# Power-Monitor-Module.net
KiCad netlist of a schematic drawn in EAGLE
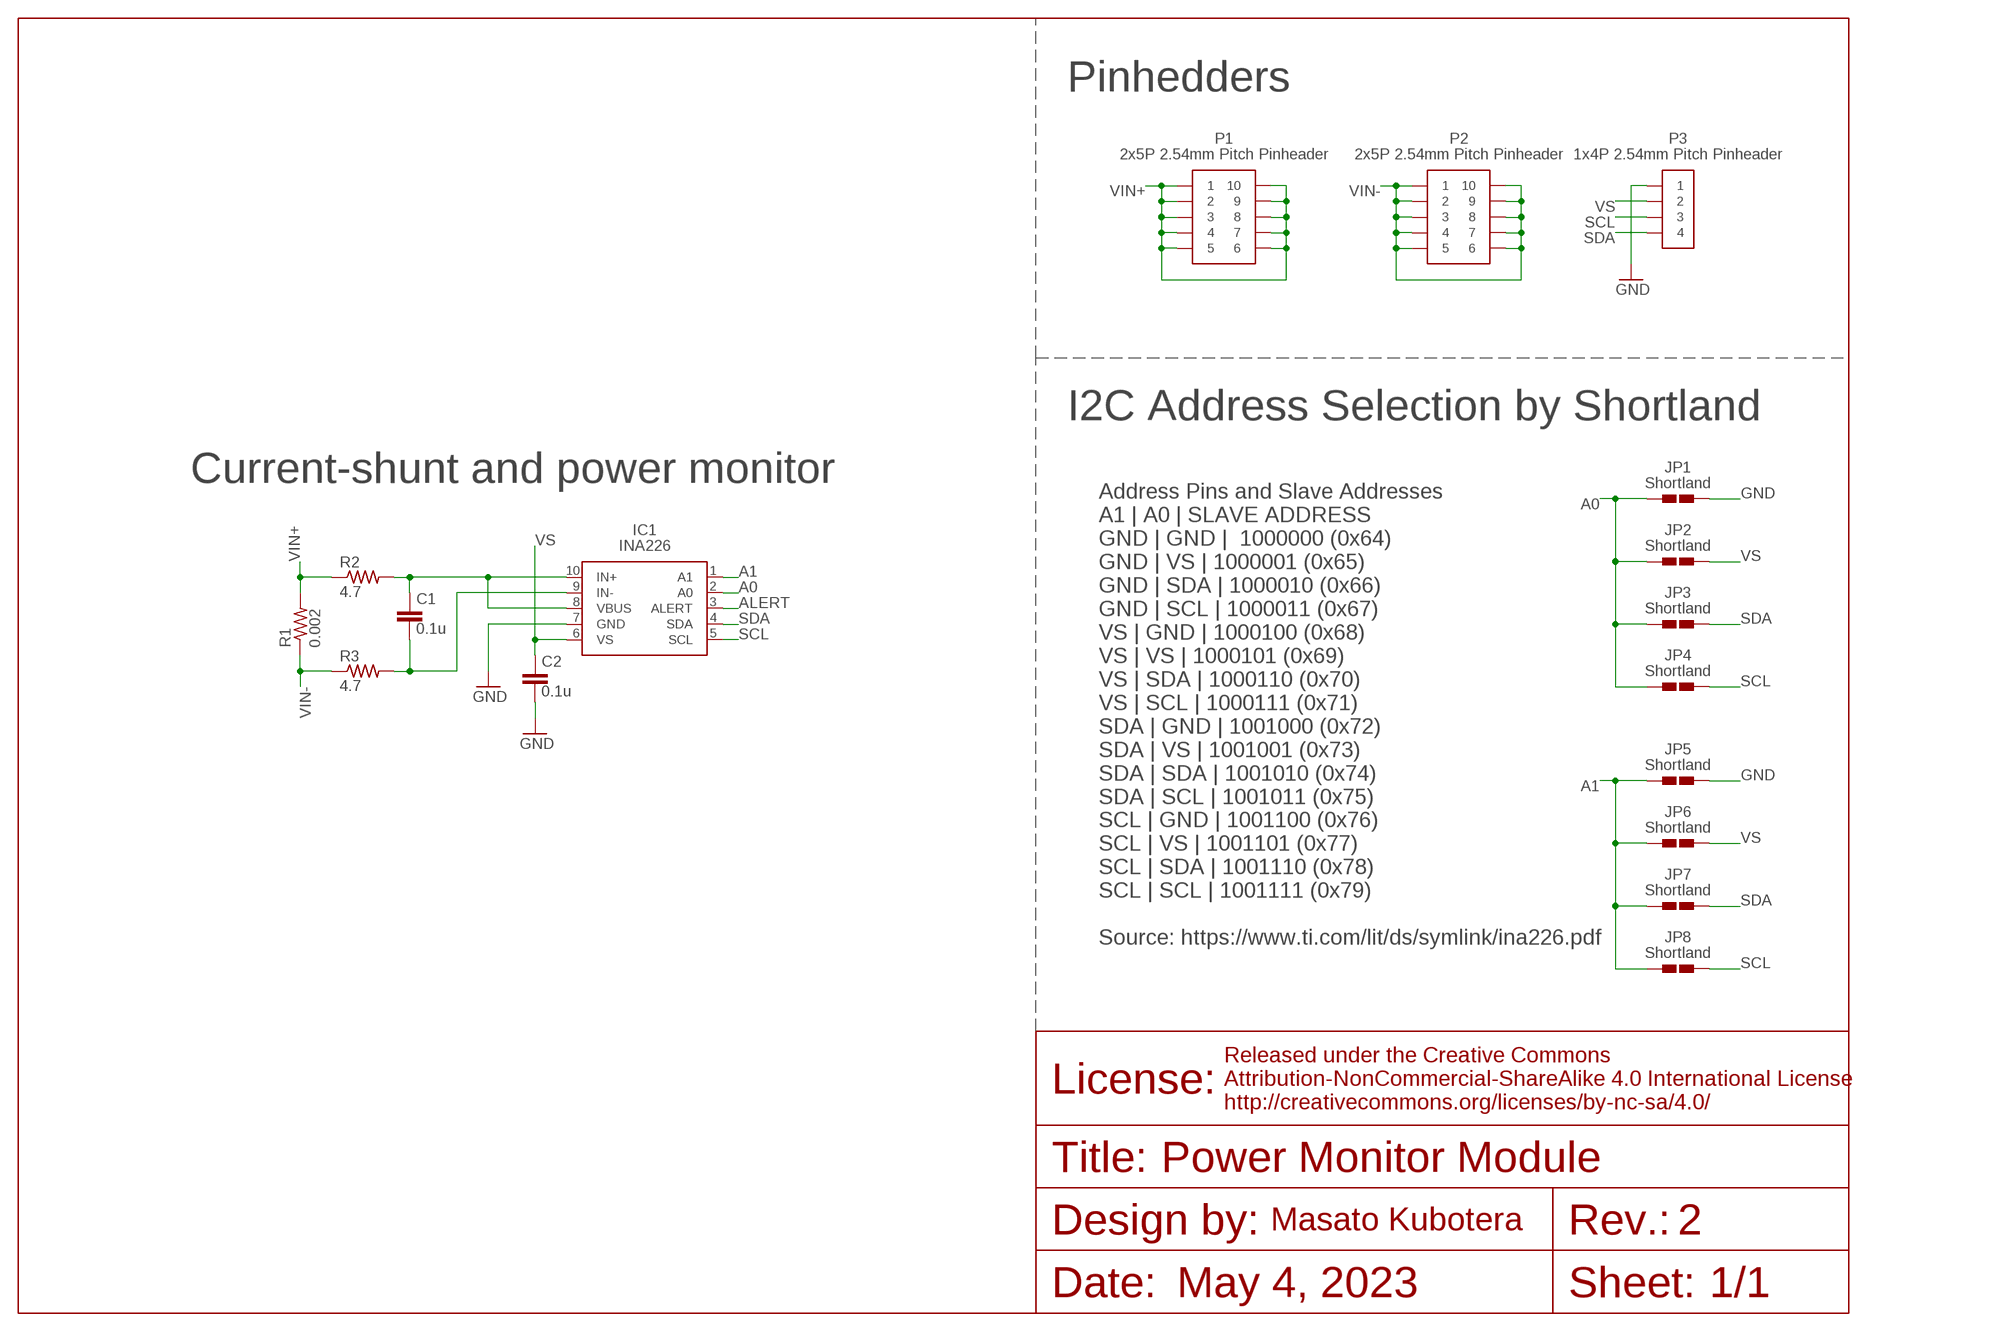
[diagram p0: schematic, sheet 1]

(export (version "E")
  (design (tool "Eeschema 10.0.6"))
  (components
    (comp (ref "C1")
      (value "0.1u")
      (footprint "eagle-import:C0402")
      (libsource (lib "eagle-import") (part "C-EUC0402"))
    )
    (comp (ref "C2")
      (value "0.1u")
      (footprint "eagle-import:C0402")
      (libsource (lib "eagle-import") (part "C-EUC0402"))
    )
    (comp (ref "IC1")
      (value "INA226")
      (footprint "eagle-import:MSOP-10")
      (libsource (lib "eagle-import") (part "INA226"))
    )
    (comp (ref "JP1")
      (value "SHORTLAND")
      (footprint "eagle-import:SHORTLAND")
      (libsource (lib "eagle-import") (part "SHORTLAND"))
    )
    (comp (ref "JP2")
      (value "SHORTLAND")
      (footprint "eagle-import:SHORTLAND")
      (libsource (lib "eagle-import") (part "SHORTLAND"))
    )
    (comp (ref "JP3")
      (value "SHORTLAND")
      (footprint "eagle-import:SHORTLAND")
      (libsource (lib "eagle-import") (part "SHORTLAND"))
    )
    (comp (ref "JP4")
      (value "SHORTLAND")
      (footprint "eagle-import:SHORTLAND")
      (libsource (lib "eagle-import") (part "SHORTLAND"))
    )
    (comp (ref "JP5")
      (value "SHORTLAND")
      (footprint "eagle-import:SHORTLAND")
      (libsource (lib "eagle-import") (part "SHORTLAND"))
    )
    (comp (ref "JP6")
      (value "SHORTLAND")
      (footprint "eagle-import:SHORTLAND")
      (libsource (lib "eagle-import") (part "SHORTLAND"))
    )
    (comp (ref "JP7")
      (value "SHORTLAND")
      (footprint "eagle-import:SHORTLAND")
      (libsource (lib "eagle-import") (part "SHORTLAND"))
    )
    (comp (ref "JP8")
      (value "SHORTLAND")
      (footprint "eagle-import:SHORTLAND")
      (libsource (lib "eagle-import") (part "SHORTLAND"))
    )
    (comp (ref "P1")
      (value "2X5P")
      (footprint "eagle-import:2X5P")
      (libsource (lib "eagle-import") (part "2X5P"))
    )
    (comp (ref "P2")
      (value "2X5P")
      (footprint "eagle-import:2X5P")
      (libsource (lib "eagle-import") (part "2X5P"))
    )
    (comp (ref "P3")
      (value "1X4P")
      (footprint "eagle-import:1X4P")
      (libsource (lib "eagle-import") (part "1X4P"))
    )
    (comp (ref "R1")
      (value "0.002")
      (footprint "eagle-import:R2512")
      (libsource (lib "eagle-import") (part "R-US_R2512"))
    )
    (comp (ref "R2")
      (value "4.7")
      (footprint "eagle-import:R0402")
      (libsource (lib "eagle-import") (part "R-US_R0402"))
    )
    (comp (ref "R3")
      (value "4.7")
      (footprint "eagle-import:R0402")
      (libsource (lib "eagle-import") (part "R-US_R0402"))
    )
  )
  (nets
    (net (code "1") (name "/A0") (class "Default")
      (node (ref "IC1") (pin "2") (pinfunction "A0_2") (pintype "bidirectional"))
      (node (ref "JP1") (pin "1") (pinfunction "1_1") (pintype "bidirectional"))
      (node (ref "JP2") (pin "1") (pinfunction "1_1") (pintype "bidirectional"))
      (node (ref "JP3") (pin "1") (pinfunction "1_1") (pintype "bidirectional"))
      (node (ref "JP4") (pin "1") (pinfunction "1_1") (pintype "bidirectional"))
    )
    (net (code "2") (name "/A1") (class "Default")
      (node (ref "IC1") (pin "1") (pinfunction "A1_1") (pintype "bidirectional"))
      (node (ref "JP5") (pin "1") (pinfunction "1_1") (pintype "bidirectional"))
      (node (ref "JP6") (pin "1") (pinfunction "1_1") (pintype "bidirectional"))
      (node (ref "JP7") (pin "1") (pinfunction "1_1") (pintype "bidirectional"))
      (node (ref "JP8") (pin "1") (pinfunction "1_1") (pintype "bidirectional"))
    )
    (net (code "3") (name "/ALERT") (class "Default")
      (node (ref "IC1") (pin "3") (pinfunction "ALERT_3") (pintype "bidirectional"))
    )
    (net (code "4") (name "/SCL") (class "Default")
      (node (ref "IC1") (pin "5") (pinfunction "SCL_5") (pintype "bidirectional"))
      (node (ref "JP4") (pin "2") (pinfunction "2_2") (pintype "bidirectional"))
      (node (ref "JP8") (pin "2") (pinfunction "2_2") (pintype "bidirectional"))
      (node (ref "P3") (pin "3") (pinfunction "3_3") (pintype "bidirectional"))
    )
    (net (code "5") (name "/SDA") (class "Default")
      (node (ref "IC1") (pin "4") (pinfunction "SDA_4") (pintype "bidirectional"))
      (node (ref "JP3") (pin "2") (pinfunction "2_2") (pintype "bidirectional"))
      (node (ref "JP7") (pin "2") (pinfunction "2_2") (pintype "bidirectional"))
      (node (ref "P3") (pin "4") (pinfunction "4_4") (pintype "bidirectional"))
    )
    (net (code "6") (name "/VIN+") (class "Default")
      (node (ref "P1") (pin "1") (pinfunction "1_1") (pintype "bidirectional"))
      (node (ref "P1") (pin "10") (pinfunction "10_10") (pintype "bidirectional"))
      (node (ref "P1") (pin "2") (pinfunction "2_2") (pintype "bidirectional"))
      (node (ref "P1") (pin "3") (pinfunction "3_3") (pintype "bidirectional"))
      (node (ref "P1") (pin "4") (pinfunction "4_4") (pintype "bidirectional"))
      (node (ref "P1") (pin "5") (pinfunction "5_5") (pintype "bidirectional"))
      (node (ref "P1") (pin "6") (pinfunction "6_6") (pintype "bidirectional"))
      (node (ref "P1") (pin "7") (pinfunction "7_7") (pintype "bidirectional"))
      (node (ref "P1") (pin "8") (pinfunction "8_8") (pintype "bidirectional"))
      (node (ref "P1") (pin "9") (pinfunction "9_9") (pintype "bidirectional"))
      (node (ref "R1") (pin "2") (pinfunction "2_2") (pintype "passive"))
      (node (ref "R2") (pin "1") (pinfunction "1_1") (pintype "passive"))
    )
    (net (code "7") (name "/VIN-") (class "Default")
      (node (ref "P2") (pin "1") (pinfunction "1_1") (pintype "bidirectional"))
      (node (ref "P2") (pin "10") (pinfunction "10_10") (pintype "bidirectional"))
      (node (ref "P2") (pin "2") (pinfunction "2_2") (pintype "bidirectional"))
      (node (ref "P2") (pin "3") (pinfunction "3_3") (pintype "bidirectional"))
      (node (ref "P2") (pin "4") (pinfunction "4_4") (pintype "bidirectional"))
      (node (ref "P2") (pin "5") (pinfunction "5_5") (pintype "bidirectional"))
      (node (ref "P2") (pin "6") (pinfunction "6_6") (pintype "bidirectional"))
      (node (ref "P2") (pin "7") (pinfunction "7_7") (pintype "bidirectional"))
      (node (ref "P2") (pin "8") (pinfunction "8_8") (pintype "bidirectional"))
      (node (ref "P2") (pin "9") (pinfunction "9_9") (pintype "bidirectional"))
      (node (ref "R1") (pin "1") (pinfunction "1_1") (pintype "passive"))
      (node (ref "R3") (pin "1") (pinfunction "1_1") (pintype "passive"))
    )
    (net (code "8") (name "/VS") (class "Default")
      (node (ref "C2") (pin "1") (pinfunction "1_1") (pintype "passive"))
      (node (ref "IC1") (pin "6") (pinfunction "VS_6") (pintype "bidirectional"))
      (node (ref "JP2") (pin "2") (pinfunction "2_2") (pintype "bidirectional"))
      (node (ref "JP6") (pin "2") (pinfunction "2_2") (pintype "bidirectional"))
      (node (ref "P3") (pin "2") (pinfunction "2_2") (pintype "bidirectional"))
    )
    (net (code "9") (name "GND") (class "Default")
      (node (ref "C2") (pin "2") (pinfunction "2_2") (pintype "passive"))
      (node (ref "IC1") (pin "7") (pinfunction "GND_7") (pintype "bidirectional"))
      (node (ref "JP1") (pin "2") (pinfunction "2_2") (pintype "bidirectional"))
      (node (ref "JP5") (pin "2") (pinfunction "2_2") (pintype "bidirectional"))
      (node (ref "P3") (pin "1") (pinfunction "1_1") (pintype "bidirectional"))
    )
    (net (code "10") (name "Net-(IC1-IN+)") (class "Default")
      (node (ref "C1") (pin "1") (pinfunction "1_1") (pintype "passive"))
      (node (ref "IC1") (pin "10") (pinfunction "IN+_10") (pintype "bidirectional"))
      (node (ref "IC1") (pin "8") (pinfunction "VBUS_8") (pintype "bidirectional"))
      (node (ref "R2") (pin "2") (pinfunction "2_2") (pintype "passive"))
    )
    (net (code "11") (name "Net-(IC1-IN-)") (class "Default")
      (node (ref "C1") (pin "2") (pinfunction "2_2") (pintype "passive"))
      (node (ref "IC1") (pin "9") (pinfunction "IN-_9") (pintype "bidirectional"))
      (node (ref "R3") (pin "2") (pinfunction "2_2") (pintype "passive"))
    )
  )
)
